# GenericCommand.net
KiCad netlist of a schematic drawn in EAGLE
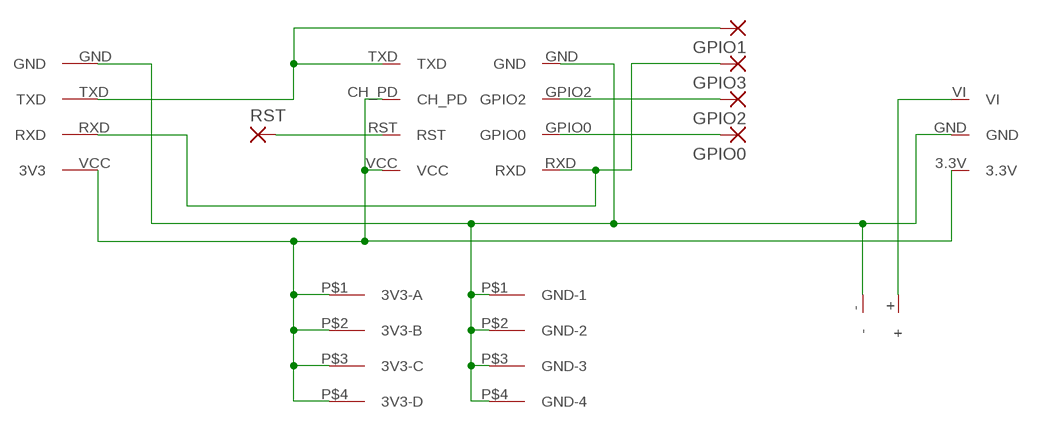
[diagram p0: schematic, sheet 1]

(export (version "E")
  (design (tool "Eeschema 10.0.6"))
  (components
    (comp (ref "GPIO0")
      (value "1,6/0,9")
      (footprint "eagle-import:1,6_0,9")
      (libsource (lib "eagle-import") (part "1,6/0,9"))
    )
    (comp (ref "GPIO1")
      (value "1,6/0,9")
      (footprint "eagle-import:1,6_0,9")
      (libsource (lib "eagle-import") (part "1,6/0,9"))
    )
    (comp (ref "GPIO2")
      (value "1,6/0,9")
      (footprint "eagle-import:1,6_0,9")
      (libsource (lib "eagle-import") (part "1,6/0,9"))
    )
    (comp (ref "GPIO3")
      (value "1,6/0,9")
      (footprint "eagle-import:1,6_0,9")
      (libsource (lib "eagle-import") (part "1,6/0,9"))
    )
    (comp (ref "RST")
      (value "1,6/0,9")
      (footprint "eagle-import:1,6_0,9")
      (libsource (lib "eagle-import") (part "1,6/0,9"))
    )
    (comp (ref "U$1")
      (value "LOW_POWER")
      (footprint "eagle-import:LOW_POWER")
      (libsource (lib "eagle-import") (part "LOW_POWER"))
    )
    (comp (ref "U$2")
      (value "3.3V-REG-SLOT")
      (footprint "eagle-import:3.3V-REG-SLOT")
      (libsource (lib "eagle-import") (part "3.3V-REG-SLOT"))
    )
    (comp (ref "U$3")
      (value "ESP-01-SLOT")
      (footprint "eagle-import:ESP-01-SLOT")
      (libsource (lib "eagle-import") (part "ESP-01-SLOT"))
    )
    (comp (ref "U$4")
      (value "CP-2102-CONN")
      (footprint "eagle-import:CP-2102-CONN")
      (libsource (lib "eagle-import") (part "CP-2102-CONN"))
    )
    (comp (ref "U$5")
      (value "3V3-4")
      (footprint "eagle-import:3.3V-4")
      (libsource (lib "eagle-import") (part "3V3-4"))
    )
    (comp (ref "U$6")
      (value "GND-4")
      (footprint "eagle-import:GND-4")
      (libsource (lib "eagle-import") (part "GND-4"))
    )
  )
  (nets
    (net (code "1") (name "Net-(GPIO0-P)") (class "Default")
      (node (ref "GPIO0") (pin "1") (pinfunction "P_1") (pintype "passive"))
      (node (ref "U$3") (pin "GPIO0") (pinfunction "GPIO0_GPIO0") (pintype "bidirectional"))
    )
    (net (code "2") (name "Net-(GPIO1-P)") (class "Default")
      (node (ref "GPIO1") (pin "1") (pinfunction "P_1") (pintype "passive"))
      (node (ref "U$3") (pin "TXD") (pinfunction "TXD_TXD") (pintype "bidirectional"))
      (node (ref "U$4") (pin "TXD") (pinfunction "TXD_TXD") (pintype "bidirectional"))
    )
    (net (code "3") (name "Net-(GPIO2-P)") (class "Default")
      (node (ref "GPIO2") (pin "1") (pinfunction "P_1") (pintype "passive"))
      (node (ref "U$3") (pin "GPIO2") (pinfunction "GPIO2_GPIO2") (pintype "bidirectional"))
    )
    (net (code "4") (name "Net-(GPIO3-P)") (class "Default")
      (node (ref "GPIO3") (pin "1") (pinfunction "P_1") (pintype "passive"))
      (node (ref "U$3") (pin "RXD") (pinfunction "RXD_RXD") (pintype "bidirectional"))
      (node (ref "U$4") (pin "RXD") (pinfunction "RXD_RXD") (pintype "bidirectional"))
    )
    (net (code "5") (name "Net-(RST-P)") (class "Default")
      (node (ref "RST") (pin "1") (pinfunction "P_1") (pintype "passive"))
      (node (ref "U$3") (pin "RST") (pinfunction "RST_RST") (pintype "bidirectional"))
    )
    (net (code "6") (name "Net-(U$1-Pad+)") (class "Default")
      (node (ref "U$1") (pin "+") (pinfunction "+_+") (pintype "bidirectional"))
      (node (ref "U$2") (pin "VI") (pinfunction "VI_VI") (pintype "bidirectional"))
    )
    (net (code "7") (name "Net-(U$4-3V3)") (class "Default")
      (node (ref "U$2") (pin "3.3V") (pinfunction "3.3V_3.3V") (pintype "bidirectional"))
      (node (ref "U$3") (pin "CH_PD") (pinfunction "CH_PD_CH_PD") (pintype "bidirectional"))
      (node (ref "U$3") (pin "VCC") (pinfunction "VCC_VCC") (pintype "bidirectional"))
      (node (ref "U$4") (pin "VCC") (pinfunction "3V3_VCC") (pintype "bidirectional"))
      (node (ref "U$5") (pin "P$1") (pinfunction "3V3-A_P$1") (pintype "bidirectional"))
      (node (ref "U$5") (pin "P$2") (pinfunction "3V3-B_P$2") (pintype "bidirectional"))
      (node (ref "U$5") (pin "P$3") (pinfunction "3V3-C_P$3") (pintype "bidirectional"))
      (node (ref "U$5") (pin "P$4") (pinfunction "3V3-D_P$4") (pintype "bidirectional"))
    )
    (net (code "8") (name "Net-(U$6-GND-1)") (class "Default")
      (node (ref "U$1") (pin "-") (pinfunction "-_-") (pintype "bidirectional"))
      (node (ref "U$2") (pin "GND") (pinfunction "GND_GND") (pintype "bidirectional"))
      (node (ref "U$3") (pin "GND") (pinfunction "GND_GND") (pintype "bidirectional"))
      (node (ref "U$4") (pin "GND") (pinfunction "GND_GND") (pintype "bidirectional"))
      (node (ref "U$6") (pin "P$1") (pinfunction "GND-1_P$1") (pintype "bidirectional"))
      (node (ref "U$6") (pin "P$2") (pinfunction "GND-2_P$2") (pintype "bidirectional"))
      (node (ref "U$6") (pin "P$3") (pinfunction "GND-3_P$3") (pintype "bidirectional"))
      (node (ref "U$6") (pin "P$4") (pinfunction "GND-4_P$4") (pintype "bidirectional"))
    )
  )
)
